# USB_CONNECTOR.net
KiCad netlist of a schematic drawn in Altium Designer
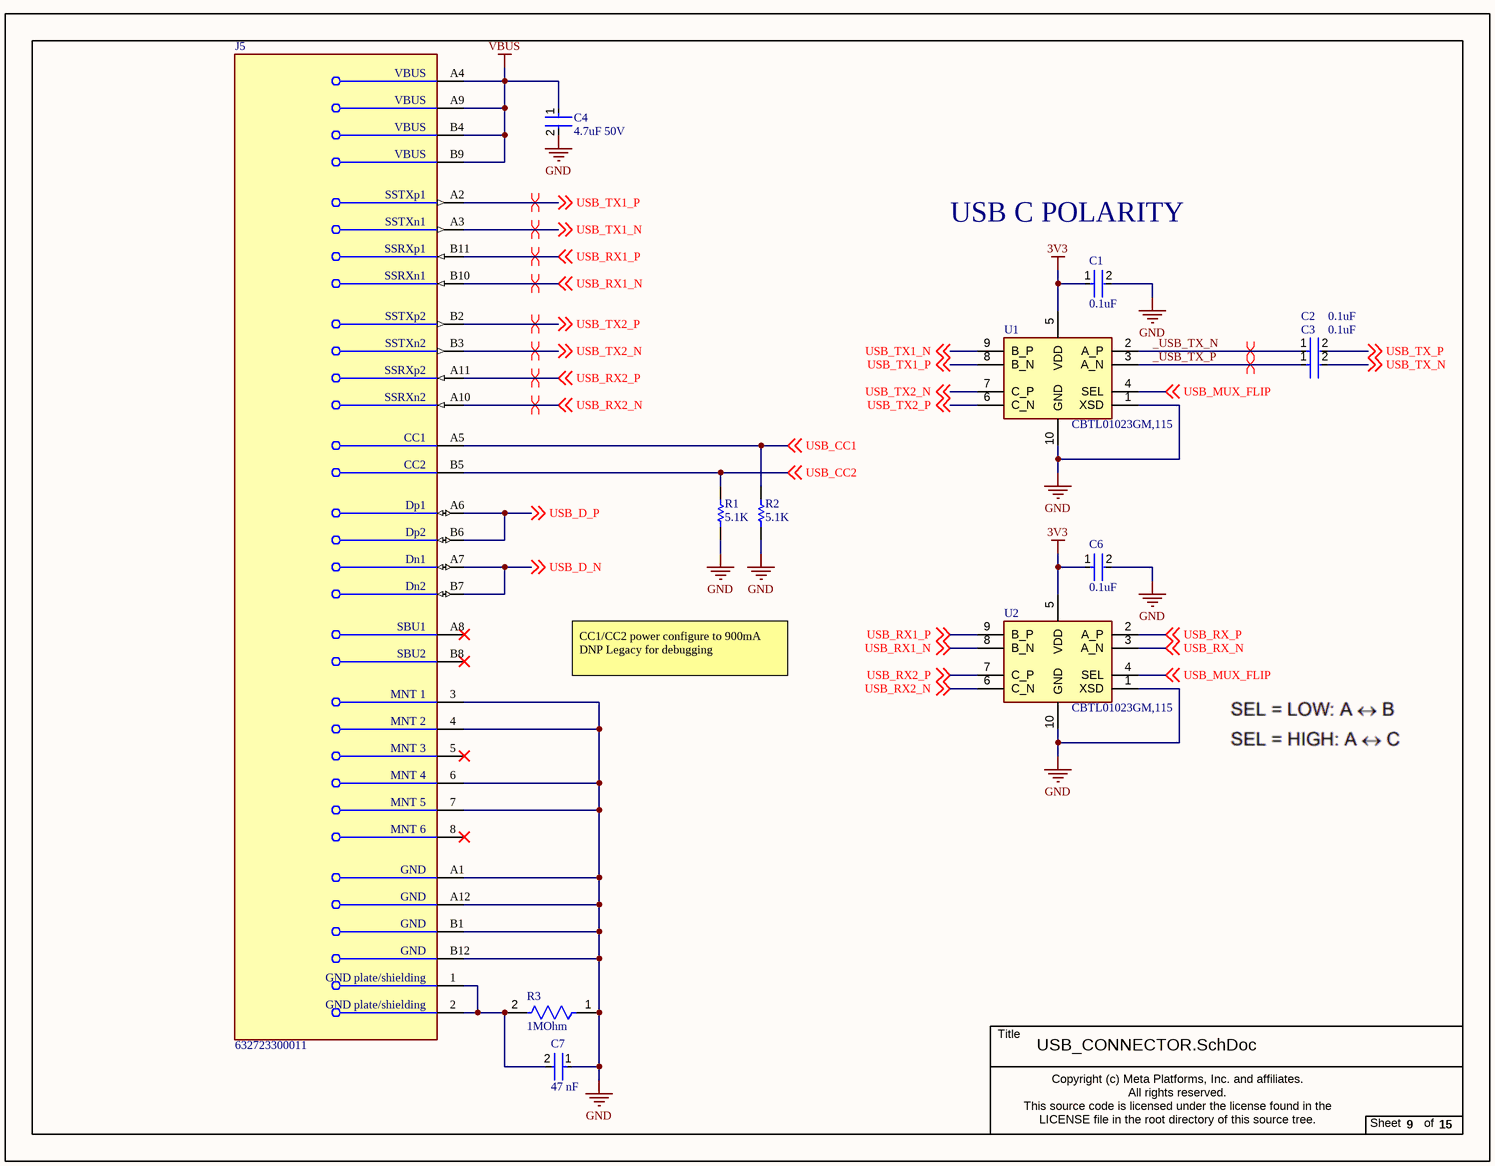
[diagram p0: USB_CONNECTOR.SchDoc]

(export (version "E")
  (design (tool "Eeschema 10.0.6"))
  (components
    (comp (ref "C1")
      (value "0.1uF")
      (footprint "FP-CC0201-BA-MFG")
      (description "CAP CER 0.1UF 6.3V X5R 0201")
      (fields (field (name "MANUFACTURER") "Yageo") (field (name "TOLERANCE") "0.1"))
      (libsource (lib "Altium Content Vault") (part "11868f565c42a9108669ba33697ecf6"))
    )
    (comp (ref "C2")
      (value "0.1uF")
      (footprint "FP-CC0201-BA-MFG")
      (description "CAP CER 0.1UF 6.3V X5R 0201")
      (fields (field (name "MANUFACTURER") "Yageo") (field (name "TOLERANCE") "0.1"))
      (libsource (lib "Altium Content Vault") (part "11868f565c42a9108669ba33697ecf6"))
    )
    (comp (ref "C3")
      (value "0.1uF")
      (footprint "FP-CC0201-BA-MFG")
      (description "CAP CER 0.1UF 6.3V X5R 0201")
      (fields (field (name "MANUFACTURER") "Yageo") (field (name "TOLERANCE") "0.1"))
      (libsource (lib "Altium Content Vault") (part "11868f565c42a9108669ba33697ecf6"))
    )
    (comp (ref "C4")
      (value "4.7uF 50V")
      (footprint "FP-C2012-125-0_2-IPC_B")
      (description "Multilayer Ceramic Capacitors 4.7μF ±10% 50V X5R SMD 0805")
      (fields (field (name "VOLTAGE") "50V") (field (name "TOLERANCE") "10%"))
      (libsource (lib "Altium Content Vault") (part "b4654b650e69147ec39a6b967a45e02"))
    )
    (comp (ref "C6")
      (value "0.1uF")
      (footprint "FP-CC0201-BA-MFG")
      (description "CAP CER 0.1UF 6.3V X5R 0201")
      (fields (field (name "MANUFACTURER") "Yageo") (field (name "TOLERANCE") "0.1"))
      (libsource (lib "Altium Content Vault") (part "11868f565c42a9108669ba33697ecf6"))
    )
    (comp (ref "C7")
      (value "47 nF")
      (footprint "FP-CC0402-MFG")
      (description "CAP CER 0.047UF 25V X7R 0402")
      (fields
        (field (name "MANUFACTURER PART NUMBER") "CC0402KRX7R8BB473")
        (field (name "MANUFACTURER") "YAGEO")
      )
      (libsource (lib "Altium Content Vault") (part "11868f565c42a9108669ba33697ecf6"))
    )
    (comp (ref "J5")
      (value "632723300011")
      (footprint "FP-632723300011-MFG")
      (description "CONN RCP USB3.1 TYPEC 24P SMD RA")
      (libsource (lib "Altium Content Vault") (part "3fbd00113238a2b64dadcbb5111ce44"))
    )
    (comp (ref "R1")
      (value "5.1K")
      (footprint "RESC1005X40X25NL05T10")
      (fields (field (name "PART NUMBER") "RC0402FR-075K1L") (field (name "MANUFACTURER") "Yageo / Phycomp"))
      (libsource (lib "Altium Content Vault") (part "RES"))
    )
    (comp (ref "R2")
      (value "5.1K")
      (footprint "RESC1005X40X25NL05T10")
      (fields (field (name "PART NUMBER") "RC0402FR-075K1L") (field (name "MANUFACTURER") "Yageo / Phycomp"))
      (libsource (lib "Altium Content Vault") (part "RES"))
    )
    (comp (ref "R3")
      (value "1MOhm")
      (footprint "FP-RMCF0402-MFG")
      (description "1MΩ ±1% 0.063W 0402 Thick Film Chip Resistor AEC-Q200 compliant")
      (fields (field (name "TOLERANCE") "1%"))
      (libsource (lib "Altium Content Vault") (part "1029c3af85768c4190bb7ad29bc67b5"))
    )
    (comp (ref "U1")
      (value "CBTL01023GM,115")
      (footprint "QFN50P200X155X50-10N")
      (description "DisplayPort, PCIe, USB Switch IC 1 Channel 10-XQFN (1.55x2)")
      (fields (field (name "MANUFACTURER") "NXP USA Inc.") (field (name "PART NUMBER") "CBTL01023GM,115"))
      (libsource (lib "Phalanx") (part "CBTL01023GM,115"))
    )
    (comp (ref "U2")
      (value "CBTL01023GM,115")
      (footprint "QFN50P200X155X50-10N")
      (description "DisplayPort, PCIe, USB Switch IC 1 Channel 10-XQFN (1.55x2)")
      (fields (field (name "MANUFACTURER") "NXP USA Inc.") (field (name "PART NUMBER") "CBTL01023GM,115"))
      (libsource (lib "Phalanx") (part "CBTL01023GM,115"))
    )
  )
  (nets
    (net (code "1") (name "/_USB_TX_N") (class "Default")
      (node (ref "C2") (pin "1") (pinfunction "1_1") (pintype "passive"))
      (node (ref "U1") (pin "2") (pinfunction "A_P_2") (pintype "passive"))
    )
    (net (code "2") (name "/_USB_TX_P") (class "Default")
      (node (ref "C3") (pin "1") (pinfunction "1_1") (pintype "passive"))
      (node (ref "U1") (pin "3") (pinfunction "A_N_3") (pintype "passive"))
    )
    (net (code "3") (name "3V3") (class "Default")
      (node (ref "C1") (pin "1") (pinfunction "1_1") (pintype "passive"))
      (node (ref "C6") (pin "1") (pinfunction "1_1") (pintype "passive"))
      (node (ref "U1") (pin "5") (pinfunction "VDD_5") (pintype "power_in"))
      (node (ref "U2") (pin "5") (pinfunction "VDD_5") (pintype "power_in"))
    )
    (net (code "4") (name "GND") (class "Default")
      (node (ref "C1") (pin "2") (pinfunction "2_2") (pintype "passive"))
      (node (ref "C4") (pin "2") (pinfunction "2_2") (pintype "passive"))
      (node (ref "C6") (pin "2") (pinfunction "2_2") (pintype "passive"))
      (node (ref "C7") (pin "1") (pinfunction "1_1") (pintype "passive"))
      (node (ref "J5") (pin "3") (pinfunction "MNT_1_3") (pintype "passive"))
      (node (ref "J5") (pin "4") (pinfunction "MNT_2_4") (pintype "passive"))
      (node (ref "J5") (pin "6") (pinfunction "MNT_4_6") (pintype "passive"))
      (node (ref "J5") (pin "7") (pinfunction "MNT_5_7") (pintype "passive"))
      (node (ref "J5") (pin "A1") (pinfunction "GND_A1") (pintype "power_in"))
      (node (ref "J5") (pin "A12") (pinfunction "GND_A12") (pintype "power_in"))
      (node (ref "J5") (pin "B1") (pinfunction "GND_B1") (pintype "power_in"))
      (node (ref "J5") (pin "B12") (pinfunction "GND_B12") (pintype "power_in"))
      (node (ref "R1") (pin "1") (pinfunction "1_1") (pintype "passive"))
      (node (ref "R2") (pin "1") (pinfunction "1_1") (pintype "passive"))
      (node (ref "R3") (pin "1") (pinfunction "1_1") (pintype "passive"))
      (node (ref "U1") (pin "1") (pinfunction "XSD_1") (pintype "passive"))
      (node (ref "U1") (pin "10") (pinfunction "GND_10") (pintype "power_in"))
      (node (ref "U2") (pin "1") (pinfunction "XSD_1") (pintype "passive"))
      (node (ref "U2") (pin "10") (pinfunction "GND_10") (pintype "power_in"))
    )
    (net (code "5") (name "Net-(C7-Pad2)") (class "Default")
      (node (ref "C7") (pin "2") (pinfunction "2_2") (pintype "passive"))
      (node (ref "J5") (pin "1") (pinfunction "GND_plate/shielding_1") (pintype "power_in"))
      (node (ref "J5") (pin "2") (pinfunction "GND_plate/shielding_2") (pintype "power_in"))
      (node (ref "R3") (pin "2") (pinfunction "2_2") (pintype "passive"))
    )
    (net (code "6") (name "USB_CC1") (class "Default")
      (node (ref "J5") (pin "A5") (pinfunction "CC1_A5") (pintype "passive"))
      (node (ref "R2") (pin "2") (pinfunction "2_2") (pintype "passive"))
    )
    (net (code "7") (name "USB_CC2") (class "Default")
      (node (ref "J5") (pin "B5") (pinfunction "CC2_B5") (pintype "passive"))
      (node (ref "R1") (pin "2") (pinfunction "2_2") (pintype "passive"))
    )
    (net (code "8") (name "USB_D_N") (class "Default")
      (node (ref "J5") (pin "A7") (pinfunction "Dn1_A7") (pintype "bidirectional"))
      (node (ref "J5") (pin "B7") (pinfunction "Dn2_B7") (pintype "bidirectional"))
    )
    (net (code "9") (name "USB_D_P") (class "Default")
      (node (ref "J5") (pin "A6") (pinfunction "Dp1_A6") (pintype "bidirectional"))
      (node (ref "J5") (pin "B6") (pinfunction "Dp2_B6") (pintype "bidirectional"))
    )
    (net (code "10") (name "USB_MUX_FLIP") (class "Default")
      (node (ref "U1") (pin "4") (pinfunction "SEL_4") (pintype "passive"))
      (node (ref "U2") (pin "4") (pinfunction "SEL_4") (pintype "passive"))
    )
    (net (code "11") (name "USB_RX1_N") (class "Default")
      (node (ref "J5") (pin "B10") (pinfunction "SSRXn1_B10") (pintype "input"))
      (node (ref "U2") (pin "8") (pinfunction "B_N_8") (pintype "passive"))
    )
    (net (code "12") (name "USB_RX1_P") (class "Default")
      (node (ref "J5") (pin "B11") (pinfunction "SSRXp1_B11") (pintype "input"))
      (node (ref "U2") (pin "9") (pinfunction "B_P_9") (pintype "passive"))
    )
    (net (code "13") (name "USB_RX2_N") (class "Default")
      (node (ref "J5") (pin "A10") (pinfunction "SSRXn2_A10") (pintype "input"))
      (node (ref "U2") (pin "6") (pinfunction "C_N_6") (pintype "passive"))
    )
    (net (code "14") (name "USB_RX2_P") (class "Default")
      (node (ref "J5") (pin "A11") (pinfunction "SSRXp2_A11") (pintype "input"))
      (node (ref "U2") (pin "7") (pinfunction "C_P_7") (pintype "passive"))
    )
    (net (code "15") (name "USB_RX_N") (class "Default")
      (node (ref "U2") (pin "3") (pinfunction "A_N_3") (pintype "passive"))
    )
    (net (code "16") (name "USB_RX_P") (class "Default")
      (node (ref "U2") (pin "2") (pinfunction "A_P_2") (pintype "passive"))
    )
    (net (code "17") (name "USB_TX1_N") (class "Default")
      (node (ref "J5") (pin "A3") (pinfunction "SSTXn1_A3") (pintype "output"))
      (node (ref "U1") (pin "9") (pinfunction "B_P_9") (pintype "passive"))
    )
    (net (code "18") (name "USB_TX1_P") (class "Default")
      (node (ref "J5") (pin "A2") (pinfunction "SSTXp1_A2") (pintype "output"))
      (node (ref "U1") (pin "8") (pinfunction "B_N_8") (pintype "passive"))
    )
    (net (code "19") (name "USB_TX2_N") (class "Default")
      (node (ref "J5") (pin "B3") (pinfunction "SSTXn2_B3") (pintype "output"))
      (node (ref "U1") (pin "7") (pinfunction "C_P_7") (pintype "passive"))
    )
    (net (code "20") (name "USB_TX2_P") (class "Default")
      (node (ref "J5") (pin "B2") (pinfunction "SSTXp2_B2") (pintype "output"))
      (node (ref "U1") (pin "6") (pinfunction "C_N_6") (pintype "passive"))
    )
    (net (code "21") (name "USB_TX_N") (class "Default")
      (node (ref "C3") (pin "2") (pinfunction "2_2") (pintype "passive"))
    )
    (net (code "22") (name "USB_TX_P") (class "Default")
      (node (ref "C2") (pin "2") (pinfunction "2_2") (pintype "passive"))
    )
    (net (code "23") (name "VBUS") (class "Default")
      (node (ref "C4") (pin "1") (pinfunction "1_1") (pintype "passive"))
      (node (ref "J5") (pin "A4") (pinfunction "VBUS_A4") (pintype "power_in"))
      (node (ref "J5") (pin "A9") (pinfunction "VBUS_A9") (pintype "power_in"))
      (node (ref "J5") (pin "B4") (pinfunction "VBUS_B4") (pintype "power_in"))
      (node (ref "J5") (pin "B9") (pinfunction "VBUS_B9") (pintype "power_in"))
    )
    (net (code "24") (name "unconnected-(J5-MNT_3-Pad5)") (class "Default")
      (node (ref "J5") (pin "5") (pinfunction "MNT_3_5") (pintype "passive+no_connect"))
    )
    (net (code "25") (name "unconnected-(J5-MNT_6-Pad8)") (class "Default")
      (node (ref "J5") (pin "8") (pinfunction "MNT_6_8") (pintype "passive+no_connect"))
    )
    (net (code "26") (name "unconnected-(J5-SBU1-PadA8)") (class "Default")
      (node (ref "J5") (pin "A8") (pinfunction "SBU1_A8") (pintype "passive+no_connect"))
    )
    (net (code "27") (name "unconnected-(J5-SBU2-PadB8)") (class "Default")
      (node (ref "J5") (pin "B8") (pinfunction "SBU2_B8") (pintype "passive+no_connect"))
    )
  )
)
